# LN_LDO.net
KiCad netlist of a schematic drawn in Altium Designer
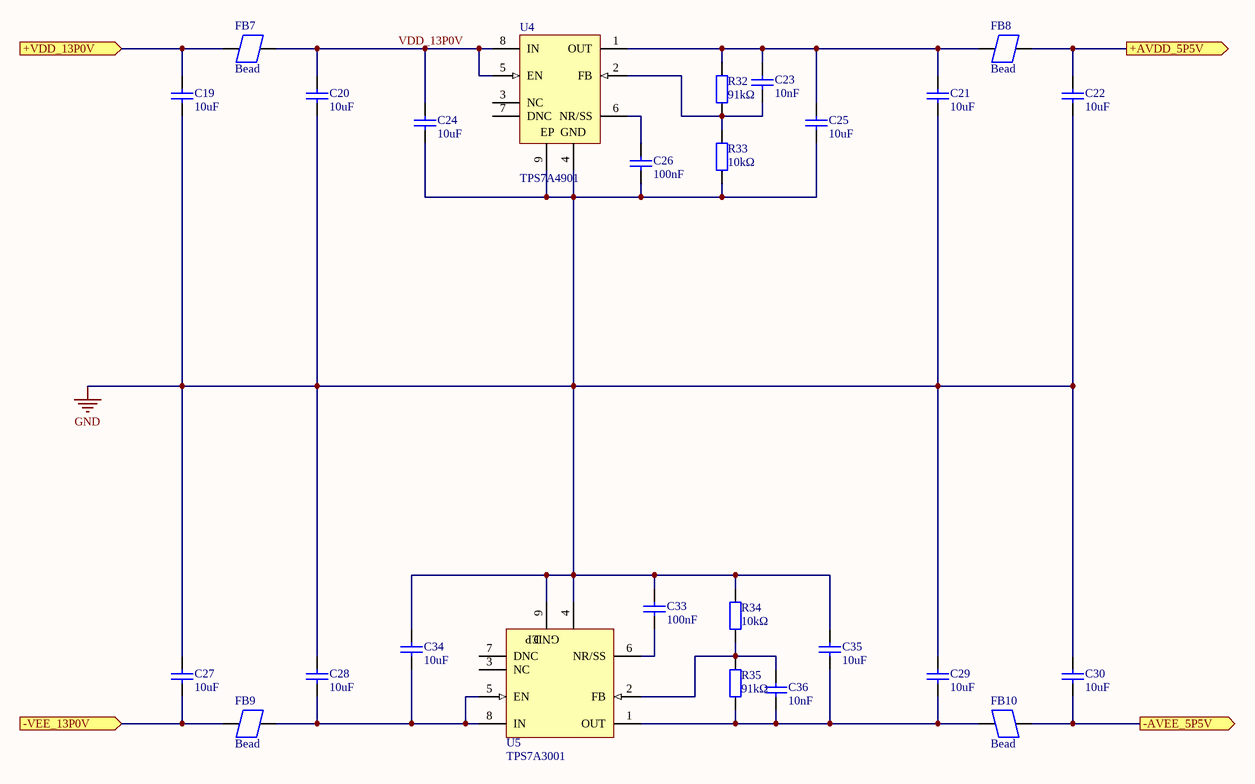
[diagram p0: LN_LDO.SchDoc]

(export (version "E")
  (design (tool "Eeschema 10.0.6"))
  (components
    (comp (ref "C19")
      (value "10uF")
      (footprint "0805_C")
      (description "贴片电容")
      (libsource (lib "Miscellaneous Devices LC") (part "0805 10uF (106) 10% 25V"))
    )
    (comp (ref "C20")
      (value "10uF")
      (footprint "0805_C")
      (description "贴片电容")
      (libsource (lib "Miscellaneous Devices LC") (part "0805 10uF (106) 10% 25V"))
    )
    (comp (ref "C21")
      (value "10uF")
      (footprint "0805_C")
      (description "贴片电容")
      (libsource (lib "Miscellaneous Devices LC") (part "0805 10uF (106) 10% 25V"))
    )
    (comp (ref "C22")
      (value "10uF")
      (footprint "0805_C")
      (description "贴片电容")
      (libsource (lib "Miscellaneous Devices LC") (part "0805 10uF (106) 10% 25V"))
    )
    (comp (ref "C23")
      (value "10nF")
      (footprint "0603_C")
      (description "贴片电容")
      (libsource (lib "Miscellaneous Devices LC") (part "0603 10nF (103) 10% 50V"))
    )
    (comp (ref "C24")
      (value "10uF")
      (footprint "0805_C")
      (description "贴片电容")
      (libsource (lib "Miscellaneous Devices LC") (part "0805 10uF (106) 10% 25V"))
    )
    (comp (ref "C25")
      (value "10uF")
      (footprint "0805_C")
      (description "贴片电容")
      (libsource (lib "Miscellaneous Devices LC") (part "0805 10uF (106) 10% 25V"))
    )
    (comp (ref "C26")
      (value "100nF")
      (footprint "0603_C")
      (description "贴片电容")
      (libsource (lib "Miscellaneous Devices LC") (part "0603 100nF (104) 10% 50V"))
    )
    (comp (ref "C27")
      (value "10uF")
      (footprint "0805_C")
      (description "贴片电容")
      (libsource (lib "Miscellaneous Devices LC") (part "0805 10uF (106) 10% 25V"))
    )
    (comp (ref "C28")
      (value "10uF")
      (footprint "0805_C")
      (description "贴片电容")
      (libsource (lib "Miscellaneous Devices LC") (part "0805 10uF (106) 10% 25V"))
    )
    (comp (ref "C29")
      (value "10uF")
      (footprint "0805_C")
      (description "贴片电容")
      (libsource (lib "Miscellaneous Devices LC") (part "0805 10uF (106) 10% 25V"))
    )
    (comp (ref "C30")
      (value "10uF")
      (footprint "0805_C")
      (description "贴片电容")
      (libsource (lib "Miscellaneous Devices LC") (part "0805 10uF (106) 10% 25V"))
    )
    (comp (ref "C33")
      (value "100nF")
      (footprint "0603_C")
      (description "贴片电容")
      (libsource (lib "Miscellaneous Devices LC") (part "0603 100nF (104) 10% 50V"))
    )
    (comp (ref "C34")
      (value "10uF")
      (footprint "0805_C")
      (description "贴片电容")
      (libsource (lib "Miscellaneous Devices LC") (part "0805 10uF (106) 10% 25V"))
    )
    (comp (ref "C35")
      (value "10uF")
      (footprint "0805_C")
      (description "贴片电容")
      (libsource (lib "Miscellaneous Devices LC") (part "0805 10uF (106) 10% 25V"))
    )
    (comp (ref "C36")
      (value "10nF")
      (footprint "0603_C")
      (description "贴片电容")
      (libsource (lib "Miscellaneous Devices LC") (part "0603 10nF (103) 10% 50V"))
    )
    (comp (ref "FB7") (value "Bead") (footprint "0805_L") (libsource (lib "OlvkLib") (part "Bead")))
    (comp (ref "FB8") (value "Bead") (footprint "0805_L") (libsource (lib "OlvkLib") (part "Bead")))
    (comp (ref "FB9") (value "Bead") (footprint "0805_L") (libsource (lib "OlvkLib") (part "Bead")))
    (comp (ref "FB10") (value "Bead") (footprint "0805_L") (libsource (lib "OlvkLib") (part "Bead")))
    (comp (ref "R32")
      (value "91kΩ")
      (footprint "0603_R")
      (description "贴片电阻")
      (libsource (lib "Miscellaneous Devices LC") (part "0603 91KΩ (9102) 1%"))
    )
    (comp (ref "R33")
      (value "10kΩ")
      (footprint "0603_R")
      (description "贴片电阻")
      (libsource (lib "Miscellaneous Devices LC") (part "0603 10KΩ (1002) 1%"))
    )
    (comp (ref "R34")
      (value "10kΩ")
      (footprint "0603_R")
      (description "贴片电阻")
      (libsource (lib "") (part "0603 10KΩ (1002) 1%_1"))
    )
    (comp (ref "R35")
      (value "91kΩ")
      (footprint "0603_R")
      (description "贴片电阻")
      (libsource (lib "") (part "0603 91KΩ (9102) 1%_1"))
    )
    (comp (ref "U4")
      (value "TPS7A4901")
      (footprint "DGN0008D_L")
      (libsource (lib "Schlib1") (part "TPS7A4901"))
    )
    (comp (ref "U5")
      (value "TPS7A3001")
      (footprint "DGN0008D_L")
      (libsource (lib "Schlib1") (part "TPS7A3001"))
    )
  )
  (nets
    (net (code "1") (name "/+AVDD_5P5V") (class "Default")
      (node (ref "C22") (pin "2") (pinfunction "2_2") (pintype "passive"))
      (node (ref "FB8") (pin "1") (pinfunction "1_1") (pintype "passive"))
    )
    (net (code "2") (name "/+VDD_13P0V") (class "Default")
      (node (ref "C19") (pin "2") (pinfunction "2_2") (pintype "passive"))
      (node (ref "FB7") (pin "2") (pinfunction "2_2") (pintype "passive"))
    )
    (net (code "3") (name "/-AVEE_5P5V") (class "Default")
      (node (ref "C30") (pin "1") (pinfunction "1_1") (pintype "passive"))
      (node (ref "FB10") (pin "1") (pinfunction "1_1") (pintype "passive"))
    )
    (net (code "4") (name "/-VEE_13P0V") (class "Default")
      (node (ref "C27") (pin "1") (pinfunction "1_1") (pintype "passive"))
      (node (ref "FB9") (pin "1") (pinfunction "1_1") (pintype "passive"))
    )
    (net (code "5") (name "/VDD_13P0V") (class "Default")
      (node (ref "C20") (pin "2") (pinfunction "2_2") (pintype "passive"))
      (node (ref "C24") (pin "2") (pinfunction "2_2") (pintype "passive"))
      (node (ref "FB7") (pin "1") (pinfunction "1_1") (pintype "passive"))
      (node (ref "U4") (pin "5") (pinfunction "EN_5") (pintype "input"))
      (node (ref "U4") (pin "8") (pinfunction "IN_8") (pintype "power_in"))
    )
    (net (code "6") (name "GND") (class "Default")
      (node (ref "C19") (pin "1") (pinfunction "1_1") (pintype "passive"))
      (node (ref "C20") (pin "1") (pinfunction "1_1") (pintype "passive"))
      (node (ref "C21") (pin "1") (pinfunction "1_1") (pintype "passive"))
      (node (ref "C22") (pin "1") (pinfunction "1_1") (pintype "passive"))
      (node (ref "C24") (pin "1") (pinfunction "1_1") (pintype "passive"))
      (node (ref "C25") (pin "1") (pinfunction "1_1") (pintype "passive"))
      (node (ref "C26") (pin "1") (pinfunction "1_1") (pintype "passive"))
      (node (ref "C27") (pin "2") (pinfunction "2_2") (pintype "passive"))
      (node (ref "C28") (pin "2") (pinfunction "2_2") (pintype "passive"))
      (node (ref "C29") (pin "2") (pinfunction "2_2") (pintype "passive"))
      (node (ref "C30") (pin "2") (pinfunction "2_2") (pintype "passive"))
      (node (ref "C33") (pin "1") (pinfunction "1_1") (pintype "passive"))
      (node (ref "C34") (pin "1") (pinfunction "1_1") (pintype "passive"))
      (node (ref "C35") (pin "1") (pinfunction "1_1") (pintype "passive"))
      (node (ref "R33") (pin "1") (pinfunction "1_1") (pintype "passive"))
      (node (ref "R34") (pin "1") (pinfunction "1_1") (pintype "passive"))
      (node (ref "U4") (pin "4") (pinfunction "GND_4") (pintype "power_in"))
      (node (ref "U4") (pin "9") (pinfunction "EP_9") (pintype "power_in"))
      (node (ref "U5") (pin "4") (pinfunction "GND_4") (pintype "power_in"))
      (node (ref "U5") (pin "9") (pinfunction "EP_9") (pintype "passive"))
    )
    (net (code "7") (name "Net-(U4-FB)") (class "Default")
      (node (ref "C23") (pin "1") (pinfunction "1_1") (pintype "passive"))
      (node (ref "R32") (pin "1") (pinfunction "1_1") (pintype "passive"))
      (node (ref "R33") (pin "2") (pinfunction "2_2") (pintype "passive"))
      (node (ref "U4") (pin "2") (pinfunction "FB_2") (pintype "input"))
    )
    (net (code "8") (name "Net-(U4-NR{slash}SS)") (class "Default")
      (node (ref "C26") (pin "2") (pinfunction "2_2") (pintype "passive"))
      (node (ref "U4") (pin "6") (pinfunction "NR/SS_6") (pintype "passive"))
    )
    (net (code "9") (name "Net-(U4-OUT)") (class "Default")
      (node (ref "C21") (pin "2") (pinfunction "2_2") (pintype "passive"))
      (node (ref "C23") (pin "2") (pinfunction "2_2") (pintype "passive"))
      (node (ref "C25") (pin "2") (pinfunction "2_2") (pintype "passive"))
      (node (ref "FB8") (pin "2") (pinfunction "2_2") (pintype "passive"))
      (node (ref "R32") (pin "2") (pinfunction "2_2") (pintype "passive"))
      (node (ref "U4") (pin "1") (pinfunction "OUT_1") (pintype "power_in"))
    )
    (net (code "10") (name "Net-(U5-EN)") (class "Default")
      (node (ref "C28") (pin "1") (pinfunction "1_1") (pintype "passive"))
      (node (ref "C34") (pin "2") (pinfunction "2_2") (pintype "passive"))
      (node (ref "FB9") (pin "2") (pinfunction "2_2") (pintype "passive"))
      (node (ref "U5") (pin "5") (pinfunction "EN_5") (pintype "input"))
      (node (ref "U5") (pin "8") (pinfunction "IN_8") (pintype "power_in"))
    )
    (net (code "11") (name "Net-(U5-FB)") (class "Default")
      (node (ref "C36") (pin "1") (pinfunction "1_1") (pintype "passive"))
      (node (ref "R34") (pin "2") (pinfunction "2_2") (pintype "passive"))
      (node (ref "R35") (pin "1") (pinfunction "1_1") (pintype "passive"))
      (node (ref "U5") (pin "2") (pinfunction "FB_2") (pintype "input"))
    )
    (net (code "12") (name "Net-(U5-NR{slash}SS)") (class "Default")
      (node (ref "C33") (pin "2") (pinfunction "2_2") (pintype "passive"))
      (node (ref "U5") (pin "6") (pinfunction "NR/SS_6") (pintype "passive"))
    )
    (net (code "13") (name "Net-(U5-OUT)") (class "Default")
      (node (ref "C29") (pin "1") (pinfunction "1_1") (pintype "passive"))
      (node (ref "C35") (pin "2") (pinfunction "2_2") (pintype "passive"))
      (node (ref "C36") (pin "2") (pinfunction "2_2") (pintype "passive"))
      (node (ref "FB10") (pin "2") (pinfunction "2_2") (pintype "passive"))
      (node (ref "R35") (pin "2") (pinfunction "2_2") (pintype "passive"))
      (node (ref "U5") (pin "1") (pinfunction "OUT_1") (pintype "power_in"))
    )
    (net (code "14") (name "unconnected-(U4-DNC-Pad7)") (class "Default")
      (node (ref "U4") (pin "7") (pinfunction "DNC_7") (pintype "passive"))
    )
    (net (code "15") (name "unconnected-(U4-NC-Pad3)") (class "Default")
      (node (ref "U4") (pin "3") (pinfunction "NC_3") (pintype "passive"))
    )
    (net (code "16") (name "unconnected-(U5-DNC-Pad7)") (class "Default")
      (node (ref "U5") (pin "7") (pinfunction "DNC_7") (pintype "passive"))
    )
    (net (code "17") (name "unconnected-(U5-NC-Pad3)") (class "Default")
      (node (ref "U5") (pin "3") (pinfunction "NC_3") (pintype "passive"))
    )
  )
)
